# OPLink_Mini.net
KiCad netlist of a schematic drawn in Altium Designer
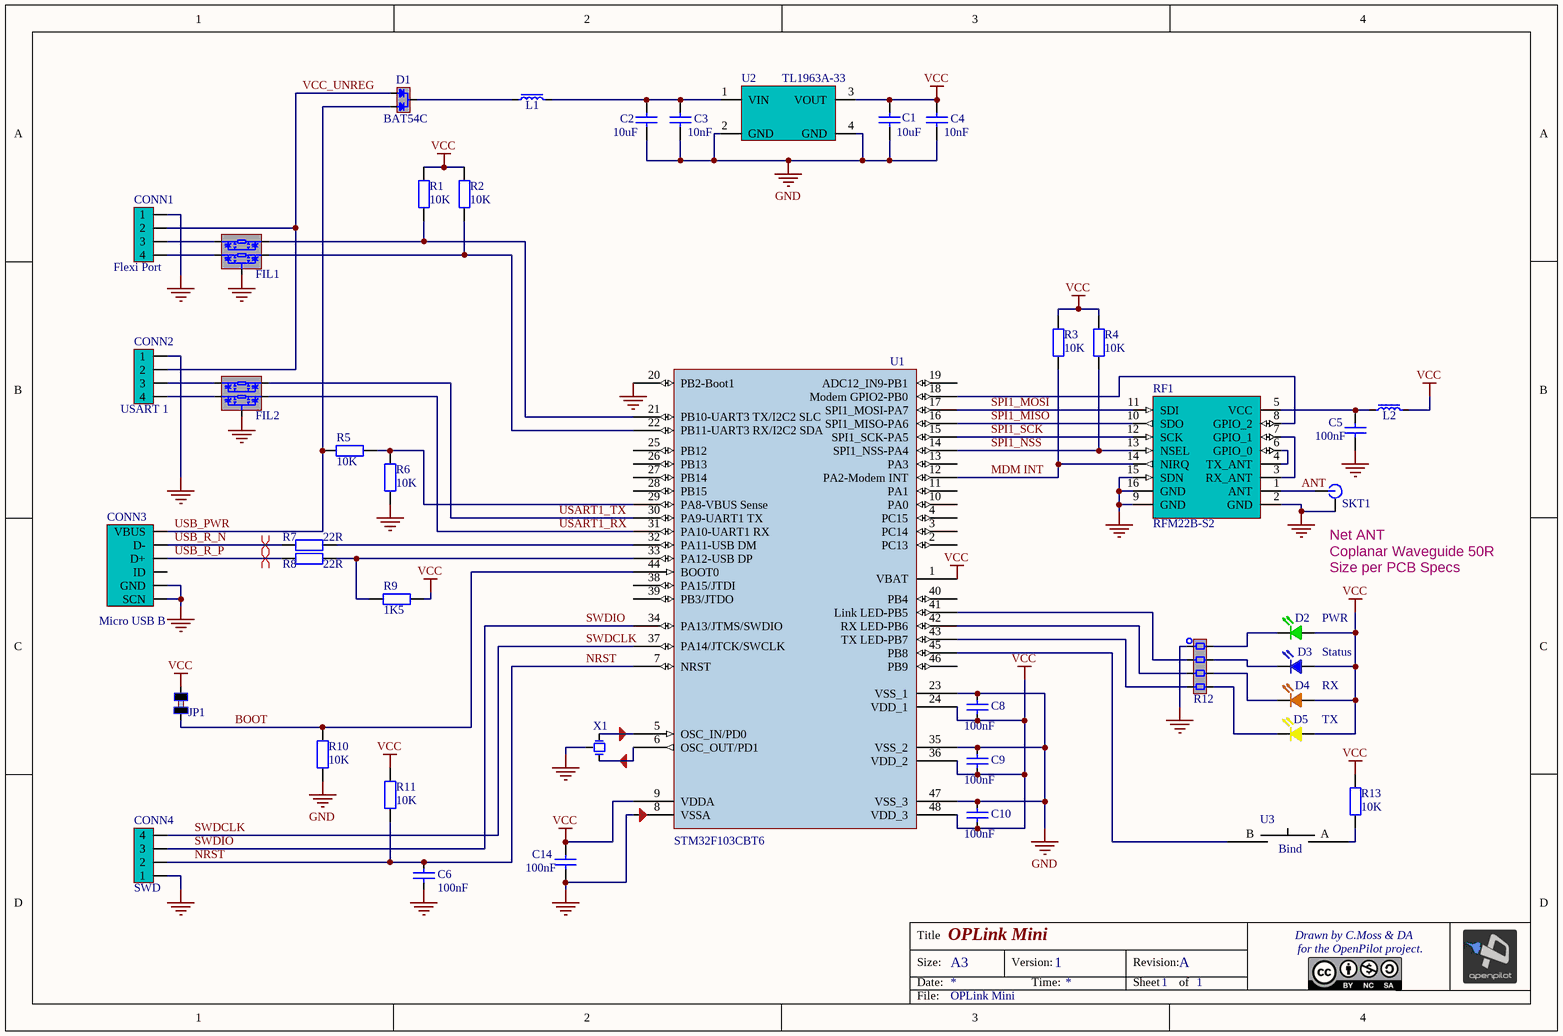
[diagram p0: OPLink Mini.SchDoc]

(export (version "E")
  (design (tool "Eeschema 10.0.6"))
  (components
    (comp (ref "C1")
      (value "10uF")
      (footprint "CAP805L")
      (description "Capacitor SMD")
      (fields (field (name "Comment") "Cap805") (field (name "PUBLISHER") "The OpenPilot Project"))
      (libsource (lib "OpenPilot") (part "Cap805"))
    )
    (comp (ref "C2")
      (value "10uF")
      (footprint "CAP805L")
      (description "Capacitor SMD")
      (fields (field (name "Comment") "Cap805") (field (name "PUBLISHER") "The OpenPilot Project"))
      (libsource (lib "OpenPilot") (part "Cap805"))
    )
    (comp (ref "C3")
      (value "10nF")
      (footprint "CAP402N")
      (description "Capacitor SMD")
      (fields (field (name "Comment") "10n") (field (name "PUBLISHER") "The OpenPilot Project"))
      (libsource (lib "OpenPilot") (part "Cap402"))
    )
    (comp (ref "C4")
      (value "10nF")
      (footprint "CAP402N")
      (description "Capacitor SMD")
      (fields (field (name "Comment") "10n") (field (name "PUBLISHER") "The OpenPilot Project"))
      (libsource (lib "OpenPilot") (part "Cap402"))
    )
    (comp (ref "C5")
      (value "100nF")
      (footprint "CAP402N")
      (description "Capacitor SMD")
      (fields (field (name "Comment") "Cap402") (field (name "PUBLISHER") "The OpenPilot Project"))
      (libsource (lib "OpenPilot") (part "Cap402"))
    )
    (comp (ref "C6")
      (value "100nF")
      (footprint "CAP402N")
      (description "Capacitor SMD")
      (fields (field (name "Comment") "Cap402") (field (name "PUBLISHER") "The OpenPilot Project"))
      (libsource (lib "") (part "Cap402_1"))
    )
    (comp (ref "C8")
      (value "100nF")
      (footprint "CAP402N")
      (description "Capacitor SMD")
      (fields (field (name "Comment") "Cap402") (field (name "PUBLISHER") "The OpenPilot Project"))
      (libsource (lib "") (part "Cap402_1"))
    )
    (comp (ref "C9")
      (value "100nF")
      (footprint "CAP402N")
      (description "Capacitor SMD")
      (fields (field (name "Comment") "Cap402") (field (name "PUBLISHER") "The OpenPilot Project"))
      (libsource (lib "") (part "Cap402_1"))
    )
    (comp (ref "C10")
      (value "100nF")
      (footprint "CAP402N")
      (description "Capacitor SMD")
      (fields (field (name "Comment") "Cap402") (field (name "PUBLISHER") "The OpenPilot Project"))
      (libsource (lib "") (part "Cap402_1"))
    )
    (comp (ref "C14")
      (value "100nF")
      (footprint "CAP402N")
      (description "Capacitor SMD")
      (fields (field (name "Comment") "Cap402") (field (name "PUBLISHER") "The OpenPilot Project"))
      (libsource (lib "OpenPilot") (part "Cap402"))
    )
    (comp (ref "CONN1")
      (value "Flexi Port")
      (footprint "JST SH 4 Pin Side Entry")
      (description "JST-SH 4-pin Side Entry Socket")
      (fields (field (name "MANUFACTURER") "Generic Components"))
      (libsource (lib "OpenPilot") (part "JST-SH 4-pin Side Entry Socket"))
    )
    (comp (ref "CONN2")
      (value "USART 1")
      (footprint "JST SH 4 Pin Side Entry")
      (description "JST-SH 4-pin Side Entry Socket")
      (fields (field (name "MANUFACTURER") "Generic Components"))
      (libsource (lib "OpenPilot") (part "JST-SH 4-pin Side Entry Socket"))
    )
    (comp (ref "CONN3")
      (value "Micro USB B")
      (footprint "Micro_USB")
      (description "USB Micro B SMT Socket")
      (fields (field (name "PUBLISHER") "The OpenPilot Project"))
      (libsource (lib "OpenPilot") (part "USB Micro B SMT"))
    )
    (comp (ref "CONN4")
      (value "SWD")
      (footprint "JST SH 4 Pin Side Entry")
      (description "JST-SH 4-pin Side Entry Socket")
      (fields (field (name "MANUFACTURER") "Generic Components"))
      (libsource (lib "") (part "JST-SH 4-pin Side Entry Socket_1"))
    )
    (comp (ref "D1")
      (value "BAT54C")
      (footprint "SOT23-3N")
      (description "Dual Diode Command Cathode")
      (libsource (lib "OpenPilot") (part "BAT54C"))
    )
    (comp (ref "D2")
      (value "PWR")
      (footprint "LED603N")
      (description "Green 603 LED")
      (libsource (lib "OpenPilot") (part "LED 603 Gr"))
    )
    (comp (ref "D3")
      (value "Status")
      (footprint "LED603N")
      (description "Blue 603 LED")
      (libsource (lib "OpenPilot") (part "LED 603 Bl"))
    )
    (comp (ref "D4")
      (value "RX")
      (footprint "LED603N")
      (description "Orange 603 LED")
      (libsource (lib "OpenPilot") (part "LED 603 Or"))
    )
    (comp (ref "D5")
      (value "TX")
      (footprint "LED603N")
      (description "Yellow 603 LED")
      (fields (field (name "PUBLISHER") "The OpenPilot Project"))
      (libsource (lib "OpenPilot") (part "LED 603 Yellow"))
    )
    (comp (ref "FIL1")
      (value "IP4256CZ5-W,115")
      (footprint "SOT-665")
      (description "IP4256CZ5-W,115 2 channel, 100R, 30pF, RF ESD Filter")
      (fields
        (field (name "MANUFACTURER") "Generic Components")
        (field (name "PUBLISHER") "The OpenPilot Project")
      )
      (libsource (lib "OpenPilot") (part "RF Filter 100R 30pF"))
    )
    (comp (ref "FIL2")
      (value "IP4256CZ5-W,115")
      (footprint "SOT-665")
      (description "IP4256CZ5-W,115 2 channel, 100R, 30pF, RF ESD Filter")
      (fields
        (field (name "MANUFACTURER") "Generic Components")
        (field (name "PUBLISHER") "The OpenPilot Project")
      )
      (libsource (lib "OpenPilot") (part "RF Filter 100R 30pF"))
    )
    (comp (ref "JP1")
      (value "2 PAD Touch JMP")
      (footprint "TOUCH JMP 2PAD")
      (description "2 Pad Touch Jumper")
      (fields (field (name "PUBLISHER") "The OpenPilot Project"))
      (libsource (lib "OpenPilot") (part "2 PAD Touch JMP"))
    )
    (comp (ref "L1")
      (value "300mA")
      (footprint "IND603N")
      (description "Ferrite Bead 300mA")
      (fields (field (name "MANUFACTURER") "Generic Components"))
      (libsource (lib "OpenPilot") (part "FerriteBead_300mA"))
    )
    (comp (ref "L2")
      (value "300mA")
      (footprint "IND603N")
      (description "Ferrite Bead 300mA")
      (fields (field (name "MANUFACTURER") "Generic Components"))
      (libsource (lib "OpenPilot") (part "FerriteBead_300mA"))
    )
    (comp (ref "R1")
      (value "10K")
      (footprint "RES402N")
      (description "Resistor SMD")
      (fields (field (name "Comment") "Res402") (field (name "PUBLISHER") "The OpenPilot Project"))
      (libsource (lib "") (part "Res402_2"))
    )
    (comp (ref "R2")
      (value "10K")
      (footprint "RES402N")
      (description "Resistor SMD")
      (fields (field (name "Comment") "Res402") (field (name "PUBLISHER") "The OpenPilot Project"))
      (libsource (lib "") (part "Res402_2"))
    )
    (comp (ref "R3")
      (value "10K")
      (footprint "RES402N")
      (description "Resistor SMD")
      (fields (field (name "Comment") "Res402") (field (name "PUBLISHER") "The OpenPilot Project"))
      (libsource (lib "") (part "Res402_2"))
    )
    (comp (ref "R4")
      (value "10K")
      (footprint "RES402N")
      (description "Resistor SMD")
      (fields (field (name "Comment") "Res402") (field (name "PUBLISHER") "The OpenPilot Project"))
      (libsource (lib "") (part "Res402_2"))
    )
    (comp (ref "R5")
      (value "10K")
      (footprint "RES402N")
      (description "Resistor SMD")
      (fields (field (name "Comment") "Res402") (field (name "PUBLISHER") "The OpenPilot Project"))
      (libsource (lib "OpenPilot") (part "Res402"))
    )
    (comp (ref "R6")
      (value "10K")
      (footprint "RES402N")
      (description "Resistor SMD")
      (fields (field (name "Comment") "Res402") (field (name "PUBLISHER") "The OpenPilot Project"))
      (libsource (lib "") (part "Res402_2"))
    )
    (comp (ref "R7")
      (value "22R")
      (footprint "RES402N")
      (description "Resistor SMD")
      (fields (field (name "Comment") "Res402") (field (name "PUBLISHER") "The OpenPilot Project"))
      (libsource (lib "OpenPilot") (part "Res402"))
    )
    (comp (ref "R8")
      (value "22R")
      (footprint "RES402N")
      (description "Resistor SMD")
      (fields (field (name "Comment") "Res402") (field (name "PUBLISHER") "The OpenPilot Project"))
      (libsource (lib "OpenPilot") (part "Res402"))
    )
    (comp (ref "R9")
      (value "1K5")
      (footprint "RES402N")
      (description "Resistor SMD")
      (fields (field (name "Comment") "Res402") (field (name "PUBLISHER") "The OpenPilot Project"))
      (libsource (lib "") (part "Res402_3"))
    )
    (comp (ref "R10")
      (value "10K")
      (footprint "RES402N")
      (description "Resistor SMD")
      (fields (field (name "Comment") "Res402") (field (name "PUBLISHER") "The OpenPilot Project"))
      (libsource (lib "") (part "Res402_1"))
    )
    (comp (ref "R11")
      (value "10K")
      (footprint "RES402N")
      (description "Resistor SMD")
      (fields (field (name "Comment") "Res402") (field (name "PUBLISHER") "The OpenPilot Project"))
      (libsource (lib "") (part "Res402_1"))
    )
    (comp (ref "R12")
      (value "Res Array 330R 1206")
      (footprint "TC164")
      (description "4 Resistor Array")
      (fields (field (name "PUBLISHER") "The OpenPilot Project"))
      (libsource (lib "OpenPilot") (part "Res Array 330R"))
    )
    (comp (ref "R13")
      (value "10K")
      (footprint "RES402N")
      (description "Resistor SMD")
      (fields (field (name "Comment") "Res402") (field (name "PUBLISHER") "The OpenPilot Project"))
      (libsource (lib "") (part "Res402_1"))
    )
    (comp (ref "RF1")
      (value "RFM22B-S2")
      (footprint "RFM22-S2")
      (description "UHF 100mW Transceiver")
      (libsource (lib "OpenPilot") (part "RFM22B-S2"))
    )
    (comp (ref "SKT1")
      (value "MMCX Thru hole")
      (footprint "MMCX_SOCKET")
      (description "MMCX Socket")
      (libsource (lib "OpenPilot") (part "MMCX Thru hole"))
    )
    (comp (ref "U1")
      (value "STM32F103CBT6")
      (footprint "STM32 48 Lead")
      (description "STM32 ARM-based 32-bit MCU with 128 Kbytes Flash, 48-pin LQFP, Industrial Temperature")
      (fields (field (name "PUBLISHER") "Altium Limited"))
      (libsource (lib "OpenPilot") (part "STM32F103CBT6"))
    )
    (comp (ref "U2")
      (value "TL1963A-33")
      (footprint "SOT223")
      (description "3.3V 1.5A LDO Regulator")
      (fields (field (name "PUBLISHER") "The OpenPilot Project"))
      (libsource (lib "OpenPilot") (part "TL1963A-33"))
    )
    (comp (ref "U3")
      (value "Bind")
      (footprint "B3U-1000P")
      (description "Push Button SMD")
      (libsource (lib "OpenPilot") (part "Push Switch Small"))
    )
    (comp (ref "X1")
      (value "8Mhz Ceralock")
      (footprint "CERALOCK 8Mhz")
      (description "Ceralock 8Mhz with caps")
      (fields (field (name "PUBLISHER") "The OpenPilot Project"))
      (libsource (lib "OpenPilot") (part "CERALOCK8"))
    )
  )
  (nets
    (net (code "1") (name "/ANT") (class "Default")
      (node (ref "RF1") (pin "1") (pinfunction "ANT_1") (pintype "passive"))
      (node (ref "SKT1") (pin "1") (pinfunction "PIN_1") (pintype "passive"))
    )
    (net (code "2") (name "/BOOT") (class "Default")
      (node (ref "JP1") (pin "1") (pinfunction "1_1") (pintype "passive"))
      (node (ref "R10") (pin "2") (pinfunction "2_2") (pintype "passive"))
      (node (ref "U1") (pin "44") (pinfunction "BOOT0_44") (pintype "input"))
    )
    (net (code "3") (name "/MDM INT") (class "Default")
      (node (ref "R3") (pin "2") (pinfunction "2_2") (pintype "passive"))
      (node (ref "RF1") (pin "14") (pinfunction "NIRQ_14") (pintype "output"))
      (node (ref "U1") (pin "12") (pinfunction "PA2-Modem_INT_12") (pintype "bidirectional"))
    )
    (net (code "4") (name "/NRST") (class "Default")
      (node (ref "C6") (pin "1") (pinfunction "1_1") (pintype "passive"))
      (node (ref "CONN4") (pin "2") (pinfunction "2_2") (pintype "passive"))
      (node (ref "R11") (pin "1") (pinfunction "1_1") (pintype "passive"))
      (node (ref "U1") (pin "7") (pinfunction "NRST_7") (pintype "bidirectional"))
    )
    (net (code "5") (name "/SPI1_MISO") (class "Default")
      (node (ref "RF1") (pin "10") (pinfunction "SDO_10") (pintype "output"))
      (node (ref "U1") (pin "16") (pinfunction "SPI1_MISO-PA6_16") (pintype "bidirectional"))
    )
    (net (code "6") (name "/SPI1_MOSI") (class "Default")
      (node (ref "RF1") (pin "11") (pinfunction "SDI_11") (pintype "input"))
      (node (ref "U1") (pin "17") (pinfunction "SPI1_MOSI-PA7_17") (pintype "bidirectional"))
    )
    (net (code "7") (name "/SPI1_NSS") (class "Default")
      (node (ref "R4") (pin "2") (pinfunction "2_2") (pintype "passive"))
      (node (ref "RF1") (pin "13") (pinfunction "NSEL_13") (pintype "input"))
      (node (ref "U1") (pin "14") (pinfunction "SPI1_NSS-PA4_14") (pintype "bidirectional"))
    )
    (net (code "8") (name "/SPI1_SCK") (class "Default")
      (node (ref "RF1") (pin "12") (pinfunction "SCK_12") (pintype "input"))
      (node (ref "U1") (pin "15") (pinfunction "SPI1_SCK-PA5_15") (pintype "bidirectional"))
    )
    (net (code "9") (name "/SWDCLK") (class "Default")
      (node (ref "CONN4") (pin "4") (pinfunction "4_4") (pintype "passive"))
      (node (ref "U1") (pin "37") (pinfunction "PA14/JTCK/SWCLK_37") (pintype "bidirectional"))
    )
    (net (code "10") (name "/SWDIO") (class "Default")
      (node (ref "CONN4") (pin "3") (pinfunction "3_3") (pintype "passive"))
      (node (ref "U1") (pin "34") (pinfunction "PA13/JTMS/SWDIO_34") (pintype "bidirectional"))
    )
    (net (code "11") (name "/USART1_RX") (class "Default")
      (node (ref "FIL2") (pin "1") (pinfunction "1_1") (pintype "passive"))
      (node (ref "U1") (pin "31") (pinfunction "PA10-UART1_RX_31") (pintype "bidirectional"))
    )
    (net (code "12") (name "/USART1_TX") (class "Default")
      (node (ref "FIL2") (pin "3") (pinfunction "3_3") (pintype "passive"))
      (node (ref "U1") (pin "30") (pinfunction "PA9-UART1_TX_30") (pintype "bidirectional"))
    )
    (net (code "13") (name "/USB_PWR") (class "Default")
      (node (ref "CONN3") (pin "1") (pinfunction "VBUS_1") (pintype "passive"))
      (node (ref "D1") (pin "2") (pinfunction "A2_2") (pintype "passive"))
      (node (ref "R5") (pin "2") (pinfunction "2_2") (pintype "passive"))
    )
    (net (code "14") (name "/USB_R_N") (class "Default")
      (node (ref "CONN3") (pin "2") (pinfunction "D-_2") (pintype "passive"))
      (node (ref "R7") (pin "2") (pinfunction "2_2") (pintype "passive"))
    )
    (net (code "15") (name "/USB_R_P") (class "Default")
      (node (ref "CONN3") (pin "3") (pinfunction "D+_3") (pintype "passive"))
      (node (ref "R8") (pin "2") (pinfunction "2_2") (pintype "passive"))
    )
    (net (code "16") (name "/VCC_UNREG") (class "Default")
      (node (ref "CONN1") (pin "2") (pinfunction "2_2") (pintype "passive"))
      (node (ref "CONN2") (pin "2") (pinfunction "2_2") (pintype "passive"))
      (node (ref "D1") (pin "1") (pinfunction "A1_1") (pintype "passive"))
    )
    (net (code "17") (name "GND") (class "Default")
      (node (ref "C1") (pin "2") (pinfunction "2_2") (pintype "passive"))
      (node (ref "C10") (pin "1") (pinfunction "1_1") (pintype "passive"))
      (node (ref "C14") (pin "2") (pinfunction "2_2") (pintype "passive"))
      (node (ref "C2") (pin "2") (pinfunction "2_2") (pintype "passive"))
      (node (ref "C3") (pin "2") (pinfunction "2_2") (pintype "passive"))
      (node (ref "C4") (pin "2") (pinfunction "2_2") (pintype "passive"))
      (node (ref "C5") (pin "2") (pinfunction "2_2") (pintype "passive"))
      (node (ref "C6") (pin "2") (pinfunction "2_2") (pintype "passive"))
      (node (ref "C8") (pin "1") (pinfunction "1_1") (pintype "passive"))
      (node (ref "C9") (pin "1") (pinfunction "1_1") (pintype "passive"))
      (node (ref "CONN1") (pin "1") (pinfunction "1_1") (pintype "passive"))
      (node (ref "CONN2") (pin "1") (pinfunction "1_1") (pintype "passive"))
      (node (ref "CONN3") (pin "0") (pinfunction "SCN_0") (pintype "passive"))
      (node (ref "CONN3") (pin "5") (pinfunction "GND_5") (pintype "passive"))
      (node (ref "CONN4") (pin "1") (pinfunction "1_1") (pintype "passive"))
      (node (ref "FIL1") (pin "2") (pinfunction "PAD_2") (pintype "passive"))
      (node (ref "FIL2") (pin "2") (pinfunction "PAD_2") (pintype "passive"))
      (node (ref "R10") (pin "1") (pinfunction "1_1") (pintype "passive"))
      (node (ref "R12") (pin "1") (pinfunction "1_1") (pintype "passive"))
      (node (ref "R6") (pin "2") (pinfunction "2_2") (pintype "passive"))
      (node (ref "RF1") (pin "15") (pinfunction "SDN_15") (pintype "input"))
      (node (ref "RF1") (pin "16") (pinfunction "GND_16") (pintype "power_in"))
      (node (ref "RF1") (pin "2") (pinfunction "GND_2") (pintype "power_in"))
      (node (ref "RF1") (pin "9") (pinfunction "GND_9") (pintype "power_in"))
      (node (ref "SKT1") (pin "2") (pinfunction "GND_2") (pintype "passive"))
      (node (ref "U1") (pin "20") (pinfunction "PB2-Boot1_20") (pintype "bidirectional"))
      (node (ref "U1") (pin "23") (pinfunction "VSS_1_23") (pintype "power_in"))
      (node (ref "U1") (pin "35") (pinfunction "VSS_2_35") (pintype "power_in"))
      (node (ref "U1") (pin "47") (pinfunction "VSS_3_47") (pintype "power_in"))
      (node (ref "U1") (pin "8") (pinfunction "VSSA_8") (pintype "power_in"))
      (node (ref "U2") (pin "2") (pinfunction "GND_2") (pintype "power_in"))
      (node (ref "U2") (pin "4") (pinfunction "GND_4") (pintype "power_in"))
      (node (ref "X1") (pin "3") (pinfunction "3_3") (pintype "passive"))
    )
    (net (code "18") (name "Net-(CONN1-Pad3)") (class "Default")
      (node (ref "CONN1") (pin "3") (pinfunction "3_3") (pintype "passive"))
      (node (ref "FIL1") (pin "4") (pinfunction "4_4") (pintype "passive"))
    )
    (net (code "19") (name "Net-(CONN1-Pad4)") (class "Default")
      (node (ref "CONN1") (pin "4") (pinfunction "4_4") (pintype "passive"))
      (node (ref "FIL1") (pin "5") (pinfunction "5_5") (pintype "passive"))
    )
    (net (code "20") (name "Net-(CONN2-Pad3)") (class "Default")
      (node (ref "CONN2") (pin "3") (pinfunction "3_3") (pintype "passive"))
      (node (ref "FIL2") (pin "4") (pinfunction "4_4") (pintype "passive"))
    )
    (net (code "21") (name "Net-(CONN2-Pad4)") (class "Default")
      (node (ref "CONN2") (pin "4") (pinfunction "4_4") (pintype "passive"))
      (node (ref "FIL2") (pin "5") (pinfunction "5_5") (pintype "passive"))
    )
    (net (code "22") (name "Net-(D1-COM)") (class "Default")
      (node (ref "D1") (pin "3") (pinfunction "COM_3") (pintype "passive"))
      (node (ref "L1") (pin "2") (pinfunction "2_2") (pintype "passive"))
    )
    (net (code "23") (name "Net-(D2-K)") (class "Default")
      (node (ref "D2") (pin "1") (pinfunction "K_1") (pintype "passive"))
      (node (ref "R12") (pin "8") (pinfunction "8_8") (pintype "passive"))
    )
    (net (code "24") (name "Net-(D3-K)") (class "Default")
      (node (ref "D3") (pin "1") (pinfunction "K_1") (pintype "passive"))
      (node (ref "R12") (pin "7") (pinfunction "7_7") (pintype "passive"))
    )
    (net (code "25") (name "Net-(D4-K)") (class "Default")
      (node (ref "D4") (pin "1") (pinfunction "K_1") (pintype "passive"))
      (node (ref "R12") (pin "6") (pinfunction "6_6") (pintype "passive"))
    )
    (net (code "26") (name "Net-(D5-K)") (class "Default")
      (node (ref "D5") (pin "1") (pinfunction "K_1") (pintype "passive"))
      (node (ref "R12") (pin "5") (pinfunction "5_5") (pintype "passive"))
    )
    (net (code "27") (name "Net-(R13-Pad1)") (class "Default")
      (node (ref "R13") (pin "1") (pinfunction "1_1") (pintype "passive"))
      (node (ref "U3") (pin "A") (pinfunction "A_A") (pintype "power_in"))
    )
    (net (code "28") (name "Net-(RF1-GPIO_0)") (class "Default")
      (node (ref "RF1") (pin "4") (pinfunction "TX_ANT_4") (pintype "passive"))
      (node (ref "RF1") (pin "6") (pinfunction "GPIO_0_6") (pintype "bidirectional"))
    )
    (net (code "29") (name "Net-(RF1-GPIO_1)") (class "Default")
      (node (ref "RF1") (pin "3") (pinfunction "RX_ANT_3") (pintype "passive"))
      (node (ref "RF1") (pin "7") (pinfunction "GPIO_1_7") (pintype "bidirectional"))
    )
    (net (code "30") (name "Net-(RF1-GPIO_2)") (class "Default")
      (node (ref "RF1") (pin "8") (pinfunction "GPIO_2_8") (pintype "bidirectional"))
      (node (ref "U1") (pin "18") (pinfunction "Modem_GPIO2-PB0_18") (pintype "bidirectional"))
    )
    (net (code "31") (name "Net-(RF1-VCC)") (class "Default")
      (node (ref "C5") (pin "1") (pinfunction "1_1") (pintype "passive"))
      (node (ref "L2") (pin "2") (pinfunction "2_2") (pintype "passive"))
      (node (ref "RF1") (pin "5") (pinfunction "VCC_5") (pintype "power_in"))
    )
    (net (code "32") (name "Net-(U1-Link_LED-PB5)") (class "Default")
      (node (ref "R12") (pin "2") (pinfunction "2_2") (pintype "passive"))
      (node (ref "U1") (pin "41") (pinfunction "Link_LED-PB5_41") (pintype "bidirectional"))
    )
    (net (code "33") (name "Net-(U1-OSC_IN{slash}PD0)") (class "Default")
      (node (ref "U1") (pin "5") (pinfunction "OSC_IN/PD0_5") (pintype "input"))
      (node (ref "X1") (pin "1") (pinfunction "1_1") (pintype "passive"))
    )
    (net (code "34") (name "Net-(U1-OSC_OUT{slash}PD1)") (class "Default")
      (node (ref "U1") (pin "6") (pinfunction "OSC_OUT/PD1_6") (pintype "output"))
      (node (ref "X1") (pin "2") (pinfunction "2_2") (pintype "passive"))
    )
    (net (code "35") (name "Net-(U1-PA8-VBUS_Sense)") (class "Default")
      (node (ref "R5") (pin "1") (pinfunction "1_1") (pintype "passive"))
      (node (ref "R6") (pin "1") (pinfunction "1_1") (pintype "passive"))
      (node (ref "U1") (pin "29") (pinfunction "PA8-VBUS_Sense_29") (pintype "bidirectional"))
    )
    (net (code "36") (name "Net-(U1-PA11-USB_DM)") (class "Default")
      (node (ref "R7") (pin "1") (pinfunction "1_1") (pintype "passive"))
      (node (ref "U1") (pin "32") (pinfunction "PA11-USB_DM_32") (pintype "bidirectional"))
    )
    (net (code "37") (name "Net-(U1-PA12-USB_DP)") (class "Default")
      (node (ref "R8") (pin "1") (pinfunction "1_1") (pintype "passive"))
      (node (ref "R9") (pin "1") (pinfunction "1_1") (pintype "passive"))
      (node (ref "U1") (pin "33") (pinfunction "PA12-USB_DP_33") (pintype "bidirectional"))
    )
    (net (code "38") (name "Net-(U1-PB8)") (class "Default")
      (node (ref "U1") (pin "45") (pinfunction "PB8_45") (pintype "bidirectional"))
      (node (ref "U3") (pin "B") (pinfunction "B_B") (pintype "power_in"))
    )
    (net (code "39") (name "Net-(U1-PB10-UART3_TX{slash}I2C2_SLC)") (class "Default")
      (node (ref "FIL1") (pin "3") (pinfunction "3_3") (pintype "passive"))
      (node (ref "R1") (pin "2") (pinfunction "2_2") (pintype "passive"))
      (node (ref "U1") (pin "21") (pinfunction "PB10-UART3_TX/I2C2_SLC_21") (pintype "bidirectional"))
    )
    (net (code "40") (name "Net-(U1-PB11-UART3_RX{slash}I2C2_SDA)") (class "Default")
      (node (ref "FIL1") (pin "1") (pinfunction "1_1") (pintype "passive"))
      (node (ref "R2") (pin "2") (pinfunction "2_2") (pintype "passive"))
      (node (ref "U1") (pin "22") (pinfunction "PB11-UART3_RX/I2C2_SDA_22") (pintype "bidirectional"))
    )
    (net (code "41") (name "Net-(U1-RX_LED-PB6)") (class "Default")
      (node (ref "R12") (pin "3") (pinfunction "3_3") (pintype "passive"))
      (node (ref "U1") (pin "42") (pinfunction "RX_LED-PB6_42") (pintype "bidirectional"))
    )
    (net (code "42") (name "Net-(U1-TX_LED-PB7)") (class "Default")
      (node (ref "R12") (pin "4") (pinfunction "4_4") (pintype "passive"))
      (node (ref "U1") (pin "43") (pinfunction "TX_LED-PB7_43") (pintype "bidirectional"))
    )
    (net (code "43") (name "Net-(U2-VIN)") (class "Default")
      (node (ref "C2") (pin "1") (pinfunction "1_1") (pintype "passive"))
      (node (ref "C3") (pin "1") (pinfunction "1_1") (pintype "passive"))
      (node (ref "L1") (pin "1") (pinfunction "1_1") (pintype "passive"))
      (node (ref "U2") (pin "1") (pinfunction "VIN_1") (pintype "power_in"))
    )
    (net (code "44") (name "VCC") (class "Default")
      (node (ref "C1") (pin "1") (pinfunction "1_1") (pintype "passive"))
      (node (ref "C10") (pin "2") (pinfunction "2_2") (pintype "passive"))
      (node (ref "C14") (pin "1") (pinfunction "1_1") (pintype "passive"))
      (node (ref "C4") (pin "1") (pinfunction "1_1") (pintype "passive"))
      (node (ref "C8") (pin "2") (pinfunction "2_2") (pintype "passive"))
      (node (ref "C9") (pin "2") (pinfunction "2_2") (pintype "passive"))
      (node (ref "D2") (pin "2") (pinfunction "A_2") (pintype "passive"))
      (node (ref "D3") (pin "2") (pinfunction "A_2") (pintype "passive"))
      (node (ref "D4") (pin "2") (pinfunction "A_2") (pintype "passive"))
      (node (ref "D5") (pin "2") (pinfunction "A_2") (pintype "passive"))
      (node (ref "JP1") (pin "2") (pinfunction "2_2") (pintype "passive"))
      (node (ref "L2") (pin "1") (pinfunction "1_1") (pintype "passive"))
      (node (ref "R1") (pin "1") (pinfunction "1_1") (pintype "passive"))
      (node (ref "R11") (pin "2") (pinfunction "2_2") (pintype "passive"))
      (node (ref "R13") (pin "2") (pinfunction "2_2") (pintype "passive"))
      (node (ref "R2") (pin "1") (pinfunction "1_1") (pintype "passive"))
      (node (ref "R3") (pin "1") (pinfunction "1_1") (pintype "passive"))
      (node (ref "R4") (pin "1") (pinfunction "1_1") (pintype "passive"))
      (node (ref "R9") (pin "2") (pinfunction "2_2") (pintype "passive"))
      (node (ref "U1") (pin "1") (pinfunction "VBAT_1") (pintype "power_in"))
      (node (ref "U1") (pin "24") (pinfunction "VDD_1_24") (pintype "power_in"))
      (node (ref "U1") (pin "36") (pinfunction "VDD_2_36") (pintype "power_in"))
      (node (ref "U1") (pin "48") (pinfunction "VDD_3_48") (pintype "power_in"))
      (node (ref "U1") (pin "9") (pinfunction "VDDA_9") (pintype "power_in"))
      (node (ref "U2") (pin "3") (pinfunction "VOUT_3") (pintype "power_in"))
    )
    (net (code "45") (name "unconnected-(CONN3-ID-Pad4)") (class "Default")
      (node (ref "CONN3") (pin "4") (pinfunction "ID_4") (pintype "passive"))
    )
    (net (code "46") (name "unconnected-(RF1-N.C-Pad1)") (class "Default")
      (node (ref "RF1") (pin "1") (pinfunction "N.C_1") (pintype "tri_state"))
    )
    (net (code "47") (name "unconnected-(RF1-N.C-Pad4)") (class "Default")
      (node (ref "RF1") (pin "4") (pinfunction "N.C_4") (pintype "tri_state"))
    )
    (net (code "48") (name "unconnected-(RF1-N.C-Pad8)") (class "Default")
      (node (ref "RF1") (pin "8") (pinfunction "N.C_8") (pintype "tri_state"))
    )
    (net (code "49") (name "unconnected-(RF1-N.C-Pad9)") (class "Default")
      (node (ref "RF1") (pin "9") (pinfunction "N.C_9") (pintype "tri_state"))
    )
    (net (code "50") (name "unconnected-(RF1-N.C-Pad14)") (class "Default")
      (node (ref "RF1") (pin "14") (pinfunction "N.C_14") (pintype "tri_state"))
    )
    (net (code "51") (name "unconnected-(U1-ADC12_IN9-PB1-Pad19)") (class "Default")
      (node (ref "U1") (pin "19") (pinfunction "ADC12_IN9-PB1_19") (pintype "bidirectional"))
    )
    (net (code "52") (name "unconnected-(U1-PA0-Pad10)") (class "Default")
      (node (ref "U1") (pin "10") (pinfunction "PA0_10") (pintype "bidirectional"))
    )
    (net (code "53") (name "unconnected-(U1-PA1-Pad11)") (class "Default")
      (node (ref "U1") (pin "11") (pinfunction "PA1_11") (pintype "bidirectional"))
    )
    (net (code "54") (name "unconnected-(U1-PA3-Pad13)") (class "Default")
      (node (ref "U1") (pin "13") (pinfunction "PA3_13") (pintype "bidirectional"))
    )
    (net (code "55") (name "unconnected-(U1-PA15{slash}JTDI-Pad38)") (class "Default")
      (node (ref "U1") (pin "38") (pinfunction "PA15/JTDI_38") (pintype "bidirectional"))
    )
    (net (code "56") (name "unconnected-(U1-PB3{slash}JTDO-Pad39)") (class "Default")
      (node (ref "U1") (pin "39") (pinfunction "PB3/JTDO_39") (pintype "bidirectional"))
    )
    (net (code "57") (name "unconnected-(U1-PB4-Pad40)") (class "Default")
      (node (ref "U1") (pin "40") (pinfunction "PB4_40") (pintype "bidirectional"))
    )
    (net (code "58") (name "unconnected-(U1-PB9-Pad46)") (class "Default")
      (node (ref "U1") (pin "46") (pinfunction "PB9_46") (pintype "bidirectional"))
    )
    (net (code "59") (name "unconnected-(U1-PB12-Pad25)") (class "Default")
      (node (ref "U1") (pin "25") (pinfunction "PB12_25") (pintype "bidirectional"))
    )
    (net (code "60") (name "unconnected-(U1-PB13-Pad26)") (class "Default")
      (node (ref "U1") (pin "26") (pinfunction "PB13_26") (pintype "bidirectional"))
    )
    (net (code "61") (name "unconnected-(U1-PB14-Pad27)") (class "Default")
      (node (ref "U1") (pin "27") (pinfunction "PB14_27") (pintype "bidirectional"))
    )
    (net (code "62") (name "unconnected-(U1-PB15-Pad28)") (class "Default")
      (node (ref "U1") (pin "28") (pinfunction "PB15_28") (pintype "bidirectional"))
    )
    (net (code "63") (name "unconnected-(U1-PC13-Pad2)") (class "Default")
      (node (ref "U1") (pin "2") (pinfunction "PC13_2") (pintype "bidirectional"))
    )
    (net (code "64") (name "unconnected-(U1-PC14-Pad3)") (class "Default")
      (node (ref "U1") (pin "3") (pinfunction "PC14_3") (pintype "bidirectional"))
    )
    (net (code "65") (name "unconnected-(U1-PC15-Pad4)") (class "Default")
      (node (ref "U1") (pin "4") (pinfunction "PC15_4") (pintype "bidirectional"))
    )
  )
)
